# Edin_Usher_V2_0.net
KiCad netlist of a schematic drawn in EAGLE
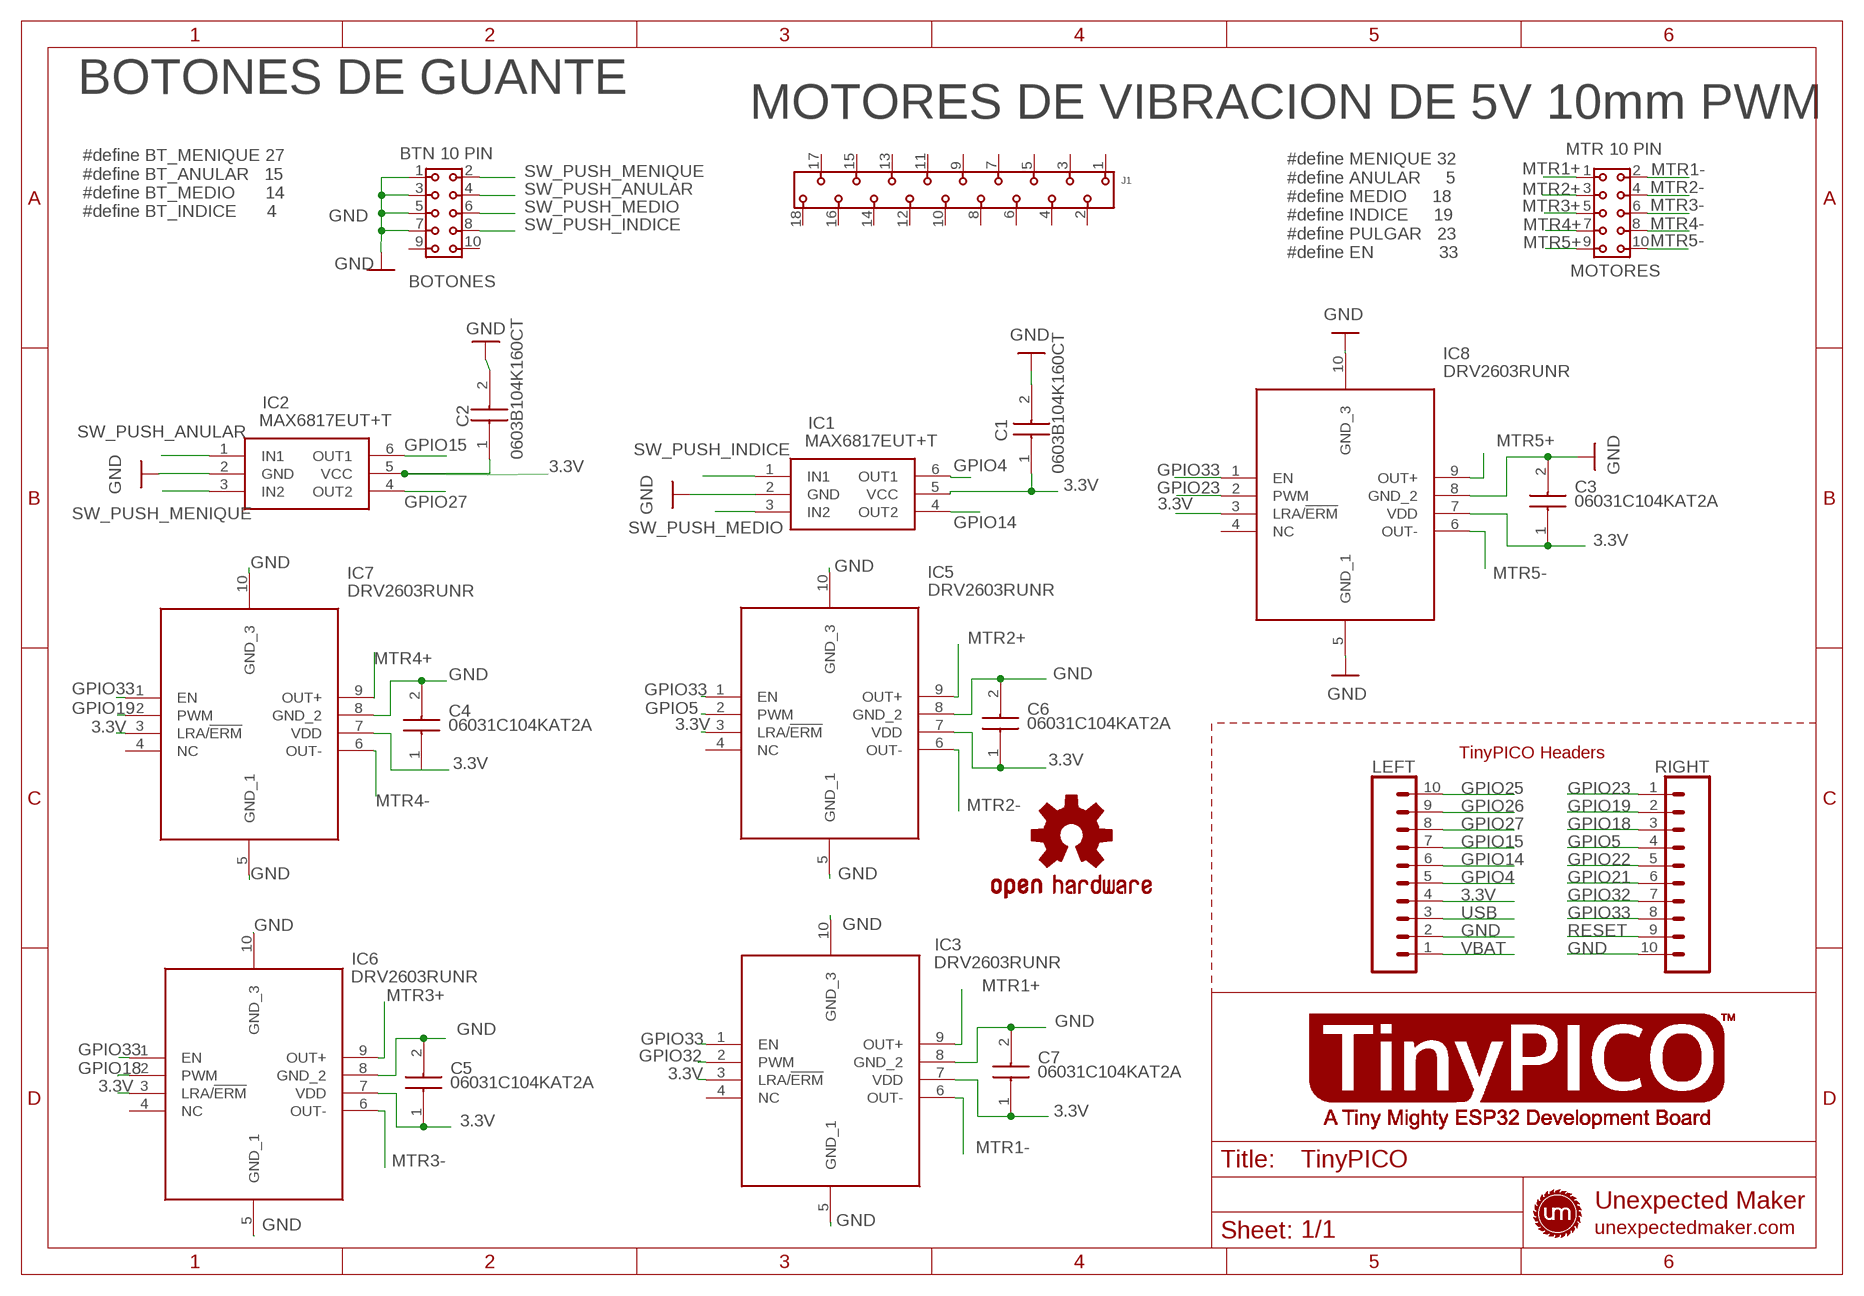
[diagram p0: schematic, sheet 1]

(export (version "E")
  (design (tool "Eeschema 10.0.6"))
  (components
    (comp (ref "BOTONES")
      (value "BTN 10 PIN")
      (footprint "eagle-import:61301021821")
      (libsource (lib "eagle-import") (part "6130XX21821_61301021821"))
    )
    (comp (ref "C1")
      (value "0603B104K160CT")
      (footprint "eagle-import:CAPC1608X87N")
      (fields (field (name "MOUSER_PART_NUMBER") "791-0603B104K160CT"))
      (libsource (lib "eagle-import") (part "0603B104K160CT"))
    )
    (comp (ref "C2")
      (value "0603B104K160CT")
      (footprint "eagle-import:CAPC1608X87N")
      (fields (field (name "MOUSER_PART_NUMBER") "791-0603B104K160CT"))
      (libsource (lib "eagle-import") (part "0603B104K160CT"))
    )
    (comp (ref "C3")
      (value "06031C104KAT2A")
      (footprint "eagle-import:CAPC1608X90N")
      (fields (field (name "MOUSER_PART_NUMBER") "581-06031C104KAT2A"))
      (libsource (lib "eagle-import") (part "06031C104KAT2A"))
    )
    (comp (ref "C4")
      (value "06031C104KAT2A")
      (footprint "eagle-import:CAPC1608X90N")
      (fields (field (name "MOUSER_PART_NUMBER") "581-06031C104KAT2A"))
      (libsource (lib "eagle-import") (part "06031C104KAT2A"))
    )
    (comp (ref "C5")
      (value "06031C104KAT2A")
      (footprint "eagle-import:CAPC1608X90N")
      (fields (field (name "MOUSER_PART_NUMBER") "581-06031C104KAT2A"))
      (libsource (lib "eagle-import") (part "06031C104KAT2A"))
    )
    (comp (ref "C6")
      (value "06031C104KAT2A")
      (footprint "eagle-import:CAPC1608X90N")
      (fields (field (name "MOUSER_PART_NUMBER") "581-06031C104KAT2A"))
      (libsource (lib "eagle-import") (part "06031C104KAT2A"))
    )
    (comp (ref "C7")
      (value "06031C104KAT2A")
      (footprint "eagle-import:CAPC1608X90N")
      (fields (field (name "MOUSER_PART_NUMBER") "581-06031C104KAT2A"))
      (libsource (lib "eagle-import") (part "06031C104KAT2A"))
    )
    (comp (ref "IC1")
      (value "MAX6817EUT+T")
      (footprint "eagle-import:SOT95P280X145-6N")
      (fields (field (name "MOUSER_PART_NUMBER") "700-MAX6817EUTT"))
      (libsource (lib "eagle-import") (part "MAX6817EUT+T"))
    )
    (comp (ref "IC2")
      (value "MAX6817EUT+T")
      (footprint "eagle-import:SOT95P280X145-6N")
      (fields (field (name "MOUSER_PART_NUMBER") "700-MAX6817EUTT"))
      (libsource (lib "eagle-import") (part "MAX6817EUT+T"))
    )
    (comp (ref "IC3")
      (value "DRV2603RUNR")
      (footprint "eagle-import:QFN50P200X200X80-10N")
      (fields (field (name "MOUSER_PART_NUMBER") "595-DRV2603RUNR"))
      (libsource (lib "eagle-import") (part "DRV2603RUNR"))
    )
    (comp (ref "IC5")
      (value "DRV2603RUNR")
      (footprint "eagle-import:QFN50P200X200X80-10N")
      (fields (field (name "MOUSER_PART_NUMBER") "595-DRV2603RUNR"))
      (libsource (lib "eagle-import") (part "DRV2603RUNR"))
    )
    (comp (ref "IC6")
      (value "DRV2603RUNR")
      (footprint "eagle-import:QFN50P200X200X80-10N")
      (fields (field (name "MOUSER_PART_NUMBER") "595-DRV2603RUNR"))
      (libsource (lib "eagle-import") (part "DRV2603RUNR"))
    )
    (comp (ref "IC7")
      (value "DRV2603RUNR")
      (footprint "eagle-import:QFN50P200X200X80-10N")
      (fields (field (name "MOUSER_PART_NUMBER") "595-DRV2603RUNR"))
      (libsource (lib "eagle-import") (part "DRV2603RUNR"))
    )
    (comp (ref "IC8")
      (value "DRV2603RUNR")
      (footprint "eagle-import:QFN50P200X200X80-10N")
      (fields (field (name "MOUSER_PART_NUMBER") "595-DRV2603RUNR"))
      (libsource (lib "eagle-import") (part "DRV2603RUNR"))
    )
    (comp (ref "J1")
      (value "490107671812")
      (footprint "eagle-import:490107671812")
      (libsource (lib "eagle-import") (part "490107671812"))
    )
    (comp (ref "LEFT")
      (value "TINYPICO_HEADER_10NO_SILK_PTH_FEMALE")
      (footprint "eagle-import:1X10_NO_SILK")
      (libsource (lib "eagle-import") (part "TINYPICO_HEADER_10NO_SILK_PTH_FEMALE"))
    )
    (comp (ref "LOGO1")
      (value "OSHW-LOGOS")
      (footprint "eagle-import:OSHW-LOGO-S")
      (libsource (lib "eagle-import") (part "OSHW-LOGOS"))
    )
    (comp (ref "MOTORES")
      (value "MTR 10 PIN")
      (footprint "eagle-import:61301021821")
      (libsource (lib "eagle-import") (part "6130XX21821_61301021821"))
    )
    (comp (ref "RIGHT")
      (value "TINYPICO_HEADER_10NO_SILK_PTH_FEMALE")
      (footprint "eagle-import:1X10_NO_SILK")
      (libsource (lib "eagle-import") (part "TINYPICO_HEADER_10NO_SILK_PTH_FEMALE"))
    )
  )
  (nets
    (net (code "1") (name "/3.3V") (class "Default")
      (node (ref "C1") (pin "1") (pinfunction "1_1") (pintype "bidirectional"))
      (node (ref "C2") (pin "1") (pinfunction "1_1") (pintype "bidirectional"))
      (node (ref "C3") (pin "1") (pinfunction "1_1") (pintype "bidirectional"))
      (node (ref "C4") (pin "1") (pinfunction "1_1") (pintype "bidirectional"))
      (node (ref "C5") (pin "1") (pinfunction "1_1") (pintype "bidirectional"))
      (node (ref "C6") (pin "1") (pinfunction "1_1") (pintype "bidirectional"))
      (node (ref "C7") (pin "1") (pinfunction "1_1") (pintype "bidirectional"))
      (node (ref "IC1") (pin "5") (pinfunction "VCC_5") (pintype "bidirectional"))
      (node (ref "IC2") (pin "5") (pinfunction "VCC_5") (pintype "bidirectional"))
      (node (ref "IC3") (pin "3") (pinfunction "LRA/~{ERM}_3") (pintype "input"))
      (node (ref "IC3") (pin "7") (pinfunction "VDD_7") (pintype "power_in"))
      (node (ref "IC5") (pin "3") (pinfunction "LRA/~{ERM}_3") (pintype "input"))
      (node (ref "IC5") (pin "7") (pinfunction "VDD_7") (pintype "power_in"))
      (node (ref "IC6") (pin "3") (pinfunction "LRA/~{ERM}_3") (pintype "input"))
      (node (ref "IC6") (pin "7") (pinfunction "VDD_7") (pintype "power_in"))
      (node (ref "IC7") (pin "3") (pinfunction "LRA/~{ERM}_3") (pintype "input"))
      (node (ref "IC7") (pin "7") (pinfunction "VDD_7") (pintype "power_in"))
      (node (ref "IC8") (pin "3") (pinfunction "LRA/~{ERM}_3") (pintype "input"))
      (node (ref "IC8") (pin "7") (pinfunction "VDD_7") (pintype "power_in"))
      (node (ref "LEFT") (pin "4") (pinfunction "4_4") (pintype "passive"))
    )
    (net (code "2") (name "/GPIO4") (class "Default")
      (node (ref "IC1") (pin "6") (pinfunction "OUT1_6") (pintype "bidirectional"))
      (node (ref "LEFT") (pin "5") (pinfunction "5_5") (pintype "passive"))
    )
    (net (code "3") (name "/GPIO5") (class "Default")
      (node (ref "IC5") (pin "2") (pinfunction "PWM_2") (pintype "input"))
      (node (ref "RIGHT") (pin "4") (pinfunction "4_4") (pintype "passive"))
    )
    (net (code "4") (name "/GPIO14") (class "Default")
      (node (ref "IC1") (pin "4") (pinfunction "OUT2_4") (pintype "bidirectional"))
      (node (ref "LEFT") (pin "6") (pinfunction "6_6") (pintype "passive"))
    )
    (net (code "5") (name "/GPIO15") (class "Default")
      (node (ref "IC2") (pin "6") (pinfunction "OUT1_6") (pintype "bidirectional"))
      (node (ref "LEFT") (pin "7") (pinfunction "7_7") (pintype "passive"))
    )
    (net (code "6") (name "/GPIO18") (class "Default")
      (node (ref "IC6") (pin "2") (pinfunction "PWM_2") (pintype "input"))
      (node (ref "RIGHT") (pin "3") (pinfunction "3_3") (pintype "passive"))
    )
    (net (code "7") (name "/GPIO19") (class "Default")
      (node (ref "IC7") (pin "2") (pinfunction "PWM_2") (pintype "input"))
      (node (ref "RIGHT") (pin "2") (pinfunction "2_2") (pintype "passive"))
    )
    (net (code "8") (name "/GPIO21") (class "Default")
      (node (ref "RIGHT") (pin "6") (pinfunction "6_6") (pintype "passive"))
    )
    (net (code "9") (name "/GPIO22") (class "Default")
      (node (ref "RIGHT") (pin "5") (pinfunction "5_5") (pintype "passive"))
    )
    (net (code "10") (name "/GPIO23") (class "Default")
      (node (ref "IC8") (pin "2") (pinfunction "PWM_2") (pintype "input"))
      (node (ref "RIGHT") (pin "1") (pinfunction "1_1") (pintype "passive"))
    )
    (net (code "11") (name "/GPIO25") (class "Default")
      (node (ref "LEFT") (pin "10") (pinfunction "10_10") (pintype "passive"))
    )
    (net (code "12") (name "/GPIO26") (class "Default")
      (node (ref "LEFT") (pin "9") (pinfunction "9_9") (pintype "passive"))
    )
    (net (code "13") (name "/GPIO27") (class "Default")
      (node (ref "IC2") (pin "4") (pinfunction "OUT2_4") (pintype "bidirectional"))
      (node (ref "LEFT") (pin "8") (pinfunction "8_8") (pintype "passive"))
    )
    (net (code "14") (name "/GPIO32") (class "Default")
      (node (ref "IC3") (pin "2") (pinfunction "PWM_2") (pintype "input"))
      (node (ref "RIGHT") (pin "7") (pinfunction "7_7") (pintype "passive"))
    )
    (net (code "15") (name "/GPIO33") (class "Default")
      (node (ref "IC3") (pin "1") (pinfunction "EN_1") (pintype "input"))
      (node (ref "IC5") (pin "1") (pinfunction "EN_1") (pintype "input"))
      (node (ref "IC6") (pin "1") (pinfunction "EN_1") (pintype "input"))
      (node (ref "IC7") (pin "1") (pinfunction "EN_1") (pintype "input"))
      (node (ref "IC8") (pin "1") (pinfunction "EN_1") (pintype "input"))
      (node (ref "RIGHT") (pin "8") (pinfunction "8_8") (pintype "passive"))
    )
    (net (code "16") (name "/MTR1+") (class "Default")
      (node (ref "IC3") (pin "9") (pinfunction "OUT+_9") (pintype "output"))
      (node (ref "MOTORES") (pin "1") (pinfunction "1_1") (pintype "passive"))
    )
    (net (code "17") (name "/MTR1-") (class "Default")
      (node (ref "IC3") (pin "6") (pinfunction "OUT-_6") (pintype "output"))
      (node (ref "MOTORES") (pin "2") (pinfunction "2_2") (pintype "passive"))
    )
    (net (code "18") (name "/MTR2+") (class "Default")
      (node (ref "IC5") (pin "9") (pinfunction "OUT+_9") (pintype "output"))
      (node (ref "MOTORES") (pin "3") (pinfunction "3_3") (pintype "passive"))
    )
    (net (code "19") (name "/MTR2-") (class "Default")
      (node (ref "IC5") (pin "6") (pinfunction "OUT-_6") (pintype "output"))
      (node (ref "MOTORES") (pin "4") (pinfunction "4_4") (pintype "passive"))
    )
    (net (code "20") (name "/MTR3+") (class "Default")
      (node (ref "IC6") (pin "9") (pinfunction "OUT+_9") (pintype "output"))
      (node (ref "MOTORES") (pin "5") (pinfunction "5_5") (pintype "passive"))
    )
    (net (code "21") (name "/MTR3-") (class "Default")
      (node (ref "IC6") (pin "6") (pinfunction "OUT-_6") (pintype "output"))
      (node (ref "MOTORES") (pin "6") (pinfunction "6_6") (pintype "passive"))
    )
    (net (code "22") (name "/MTR4+") (class "Default")
      (node (ref "IC7") (pin "9") (pinfunction "OUT+_9") (pintype "output"))
      (node (ref "MOTORES") (pin "7") (pinfunction "7_7") (pintype "passive"))
    )
    (net (code "23") (name "/MTR4-") (class "Default")
      (node (ref "IC7") (pin "6") (pinfunction "OUT-_6") (pintype "output"))
      (node (ref "MOTORES") (pin "8") (pinfunction "8_8") (pintype "passive"))
    )
    (net (code "24") (name "/MTR5+") (class "Default")
      (node (ref "IC8") (pin "9") (pinfunction "OUT+_9") (pintype "output"))
      (node (ref "MOTORES") (pin "9") (pinfunction "9_9") (pintype "passive"))
    )
    (net (code "25") (name "/MTR5-") (class "Default")
      (node (ref "IC8") (pin "6") (pinfunction "OUT-_6") (pintype "output"))
      (node (ref "MOTORES") (pin "10") (pinfunction "10_10") (pintype "passive"))
    )
    (net (code "26") (name "/RESET") (class "Default")
      (node (ref "RIGHT") (pin "9") (pinfunction "9_9") (pintype "passive"))
    )
    (net (code "27") (name "/SW_PUSH_ANULAR") (class "Default")
      (node (ref "BOTONES") (pin "4") (pinfunction "4_4") (pintype "passive"))
      (node (ref "IC2") (pin "1") (pinfunction "IN1_1") (pintype "bidirectional"))
    )
    (net (code "28") (name "/SW_PUSH_INDICE") (class "Default")
      (node (ref "BOTONES") (pin "8") (pinfunction "8_8") (pintype "passive"))
      (node (ref "IC1") (pin "1") (pinfunction "IN1_1") (pintype "bidirectional"))
    )
    (net (code "29") (name "/SW_PUSH_MEDIO") (class "Default")
      (node (ref "BOTONES") (pin "6") (pinfunction "6_6") (pintype "passive"))
      (node (ref "IC1") (pin "3") (pinfunction "IN2_3") (pintype "bidirectional"))
    )
    (net (code "30") (name "/SW_PUSH_MENIQUE") (class "Default")
      (node (ref "BOTONES") (pin "2") (pinfunction "2_2") (pintype "passive"))
      (node (ref "IC2") (pin "3") (pinfunction "IN2_3") (pintype "bidirectional"))
    )
    (net (code "31") (name "/USB") (class "Default")
      (node (ref "LEFT") (pin "3") (pinfunction "3_3") (pintype "passive"))
    )
    (net (code "32") (name "/VBAT") (class "Default")
      (node (ref "LEFT") (pin "1") (pinfunction "1_1") (pintype "passive"))
    )
    (net (code "33") (name "GND") (class "Default")
      (node (ref "BOTONES") (pin "1") (pinfunction "1_1") (pintype "passive"))
      (node (ref "BOTONES") (pin "3") (pinfunction "3_3") (pintype "passive"))
      (node (ref "BOTONES") (pin "5") (pinfunction "5_5") (pintype "passive"))
      (node (ref "BOTONES") (pin "7") (pinfunction "7_7") (pintype "passive"))
      (node (ref "C1") (pin "2") (pinfunction "2_2") (pintype "bidirectional"))
      (node (ref "C2") (pin "2") (pinfunction "2_2") (pintype "bidirectional"))
      (node (ref "C3") (pin "2") (pinfunction "2_2") (pintype "bidirectional"))
      (node (ref "C4") (pin "2") (pinfunction "2_2") (pintype "bidirectional"))
      (node (ref "C5") (pin "2") (pinfunction "2_2") (pintype "bidirectional"))
      (node (ref "C6") (pin "2") (pinfunction "2_2") (pintype "bidirectional"))
      (node (ref "C7") (pin "2") (pinfunction "2_2") (pintype "bidirectional"))
      (node (ref "IC1") (pin "2") (pinfunction "GND_2") (pintype "bidirectional"))
      (node (ref "IC2") (pin "2") (pinfunction "GND_2") (pintype "bidirectional"))
      (node (ref "IC3") (pin "10") (pinfunction "GND_3_10") (pintype "power_in"))
      (node (ref "IC3") (pin "5") (pinfunction "GND_1_5") (pintype "power_in"))
      (node (ref "IC3") (pin "8") (pinfunction "GND_2_8") (pintype "power_in"))
      (node (ref "IC5") (pin "10") (pinfunction "GND_3_10") (pintype "power_in"))
      (node (ref "IC5") (pin "5") (pinfunction "GND_1_5") (pintype "power_in"))
      (node (ref "IC5") (pin "8") (pinfunction "GND_2_8") (pintype "power_in"))
      (node (ref "IC6") (pin "10") (pinfunction "GND_3_10") (pintype "power_in"))
      (node (ref "IC6") (pin "5") (pinfunction "GND_1_5") (pintype "power_in"))
      (node (ref "IC6") (pin "8") (pinfunction "GND_2_8") (pintype "power_in"))
      (node (ref "IC7") (pin "10") (pinfunction "GND_3_10") (pintype "power_in"))
      (node (ref "IC7") (pin "5") (pinfunction "GND_1_5") (pintype "power_in"))
      (node (ref "IC7") (pin "8") (pinfunction "GND_2_8") (pintype "power_in"))
      (node (ref "IC8") (pin "10") (pinfunction "GND_3_10") (pintype "power_in"))
      (node (ref "IC8") (pin "5") (pinfunction "GND_1_5") (pintype "power_in"))
      (node (ref "IC8") (pin "8") (pinfunction "GND_2_8") (pintype "power_in"))
      (node (ref "LEFT") (pin "2") (pinfunction "2_2") (pintype "passive"))
      (node (ref "RIGHT") (pin "10") (pinfunction "10_10") (pintype "passive"))
    )
    (net (code "34") (name "unconnected-(BOTONES-Pad9)") (class "Default")
      (node (ref "BOTONES") (pin "9") (pinfunction "9_9") (pintype "passive"))
    )
    (net (code "35") (name "unconnected-(BOTONES-Pad10)") (class "Default")
      (node (ref "BOTONES") (pin "10") (pinfunction "10_10") (pintype "passive"))
    )
    (net (code "36") (name "unconnected-(IC3-NC-Pad4)") (class "Default")
      (node (ref "IC3") (pin "4") (pinfunction "NC_4") (pintype "no_connect"))
    )
    (net (code "37") (name "unconnected-(IC5-NC-Pad4)") (class "Default")
      (node (ref "IC5") (pin "4") (pinfunction "NC_4") (pintype "no_connect"))
    )
    (net (code "38") (name "unconnected-(IC6-NC-Pad4)") (class "Default")
      (node (ref "IC6") (pin "4") (pinfunction "NC_4") (pintype "no_connect"))
    )
    (net (code "39") (name "unconnected-(IC7-NC-Pad4)") (class "Default")
      (node (ref "IC7") (pin "4") (pinfunction "NC_4") (pintype "no_connect"))
    )
    (net (code "40") (name "unconnected-(IC8-NC-Pad4)") (class "Default")
      (node (ref "IC8") (pin "4") (pinfunction "NC_4") (pintype "no_connect"))
    )
    (net (code "41") (name "unconnected-(J1-Pad1)") (class "Default")
      (node (ref "J1") (pin "1") (pinfunction "1_1") (pintype "passive"))
    )
    (net (code "42") (name "unconnected-(J1-Pad2)") (class "Default")
      (node (ref "J1") (pin "2") (pinfunction "2_2") (pintype "passive"))
    )
    (net (code "43") (name "unconnected-(J1-Pad3)") (class "Default")
      (node (ref "J1") (pin "3") (pinfunction "3_3") (pintype "passive"))
    )
    (net (code "44") (name "unconnected-(J1-Pad4)") (class "Default")
      (node (ref "J1") (pin "4") (pinfunction "4_4") (pintype "passive"))
    )
    (net (code "45") (name "unconnected-(J1-Pad5)") (class "Default")
      (node (ref "J1") (pin "5") (pinfunction "5_5") (pintype "passive"))
    )
    (net (code "46") (name "unconnected-(J1-Pad6)") (class "Default")
      (node (ref "J1") (pin "6") (pinfunction "6_6") (pintype "passive"))
    )
    (net (code "47") (name "unconnected-(J1-Pad7)") (class "Default")
      (node (ref "J1") (pin "7") (pinfunction "7_7") (pintype "passive"))
    )
    (net (code "48") (name "unconnected-(J1-Pad8)") (class "Default")
      (node (ref "J1") (pin "8") (pinfunction "8_8") (pintype "passive"))
    )
    (net (code "49") (name "unconnected-(J1-Pad9)") (class "Default")
      (node (ref "J1") (pin "9") (pinfunction "9_9") (pintype "passive"))
    )
    (net (code "50") (name "unconnected-(J1-Pad10)") (class "Default")
      (node (ref "J1") (pin "10") (pinfunction "10_10") (pintype "passive"))
    )
    (net (code "51") (name "unconnected-(J1-Pad11)") (class "Default")
      (node (ref "J1") (pin "11") (pinfunction "11_11") (pintype "passive"))
    )
    (net (code "52") (name "unconnected-(J1-Pad12)") (class "Default")
      (node (ref "J1") (pin "12") (pinfunction "12_12") (pintype "passive"))
    )
    (net (code "53") (name "unconnected-(J1-Pad13)") (class "Default")
      (node (ref "J1") (pin "13") (pinfunction "13_13") (pintype "passive"))
    )
    (net (code "54") (name "unconnected-(J1-Pad14)") (class "Default")
      (node (ref "J1") (pin "14") (pinfunction "14_14") (pintype "passive"))
    )
    (net (code "55") (name "unconnected-(J1-Pad15)") (class "Default")
      (node (ref "J1") (pin "15") (pinfunction "15_15") (pintype "passive"))
    )
    (net (code "56") (name "unconnected-(J1-Pad16)") (class "Default")
      (node (ref "J1") (pin "16") (pinfunction "16_16") (pintype "passive"))
    )
    (net (code "57") (name "unconnected-(J1-Pad17)") (class "Default")
      (node (ref "J1") (pin "17") (pinfunction "17_17") (pintype "passive"))
    )
    (net (code "58") (name "unconnected-(J1-Pad18)") (class "Default")
      (node (ref "J1") (pin "18") (pinfunction "18_18") (pintype "passive"))
    )
  )
)
